# SCH_555-Circuit_2025-12-09_1.net
KiCad netlist of a schematic drawn in EasyEDA
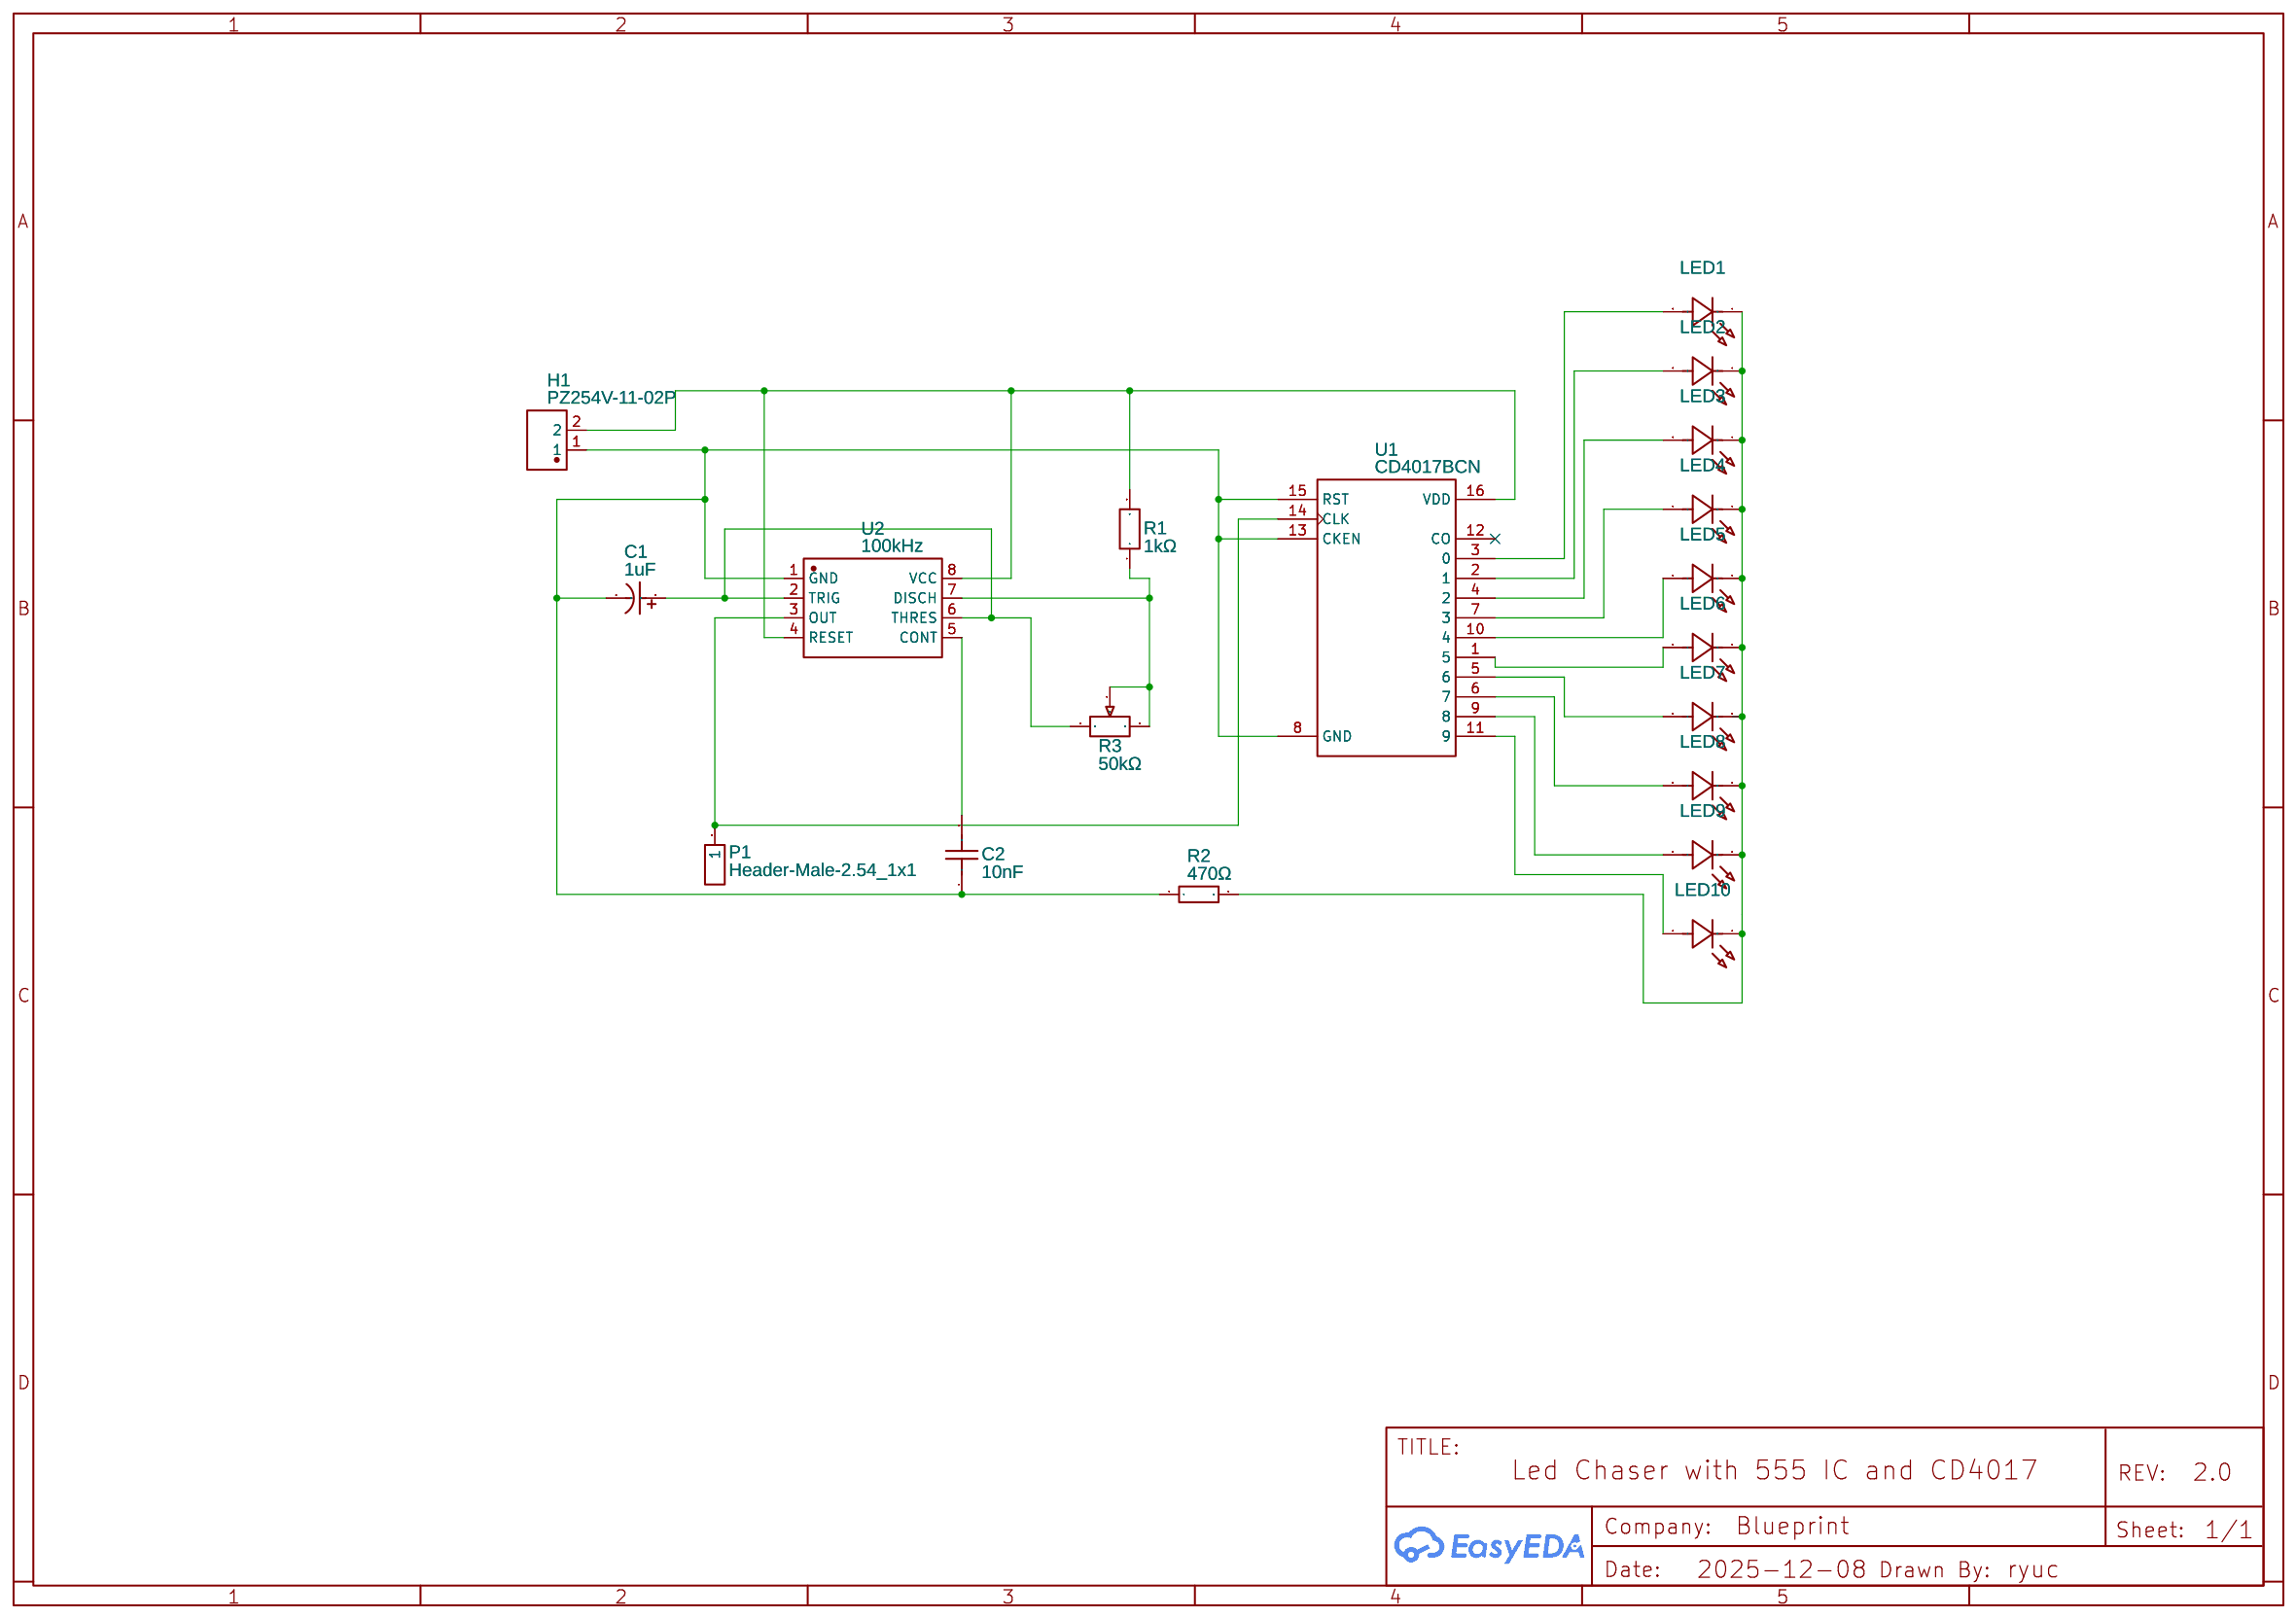
[diagram p0: schematic sheet]

(export (version "E")
  (design (tool "Eeschema 10.0.6"))
  (components
    (comp (ref "C1")
      (value "1uF")
      (fields (field (name "Manufacturer Part") "KF010M050C110A") (field (name "Manufacturer") "CapXon(丰宾)"))
      (libsource (lib "") (part "KF010M050C110A"))
    )
    (comp (ref "C2")
      (value "10nF")
      (fields (field (name "Manufacturer Part") "N09F1B103MN0B0S0N0") (field (name "Manufacturer") "STE(松田)"))
      (libsource (lib "") (part "N09F1B103MN0B0S0N0"))
    )
    (comp (ref "H1")
      (value "PZ254V-11-02P")
      (fields (field (name "Manufacturer") "XFCN(兴飞)"))
      (libsource (lib "") (part "PZ254V-11-02P"))
    )
    (comp (ref "LED1")
      (value "XL-502UWC")
      (fields (field (name "Manufacturer") "XINGLIGHT(成兴光)"))
      (libsource (lib "") (part "XL-502UWC"))
    )
    (comp (ref "LED2")
      (value "XL-502UWC")
      (fields (field (name "Manufacturer") "XINGLIGHT(成兴光)"))
      (libsource (lib "") (part "XL-502UWC"))
    )
    (comp (ref "LED3")
      (value "XL-502UWC")
      (fields (field (name "Manufacturer") "XINGLIGHT(成兴光)"))
      (libsource (lib "") (part "XL-502UWC"))
    )
    (comp (ref "LED4")
      (value "XL-502UWC")
      (fields (field (name "Manufacturer") "XINGLIGHT(成兴光)"))
      (libsource (lib "") (part "XL-502UWC"))
    )
    (comp (ref "LED5")
      (value "XL-502UWC")
      (fields (field (name "Manufacturer") "XINGLIGHT(成兴光)"))
      (libsource (lib "") (part "XL-502UWC"))
    )
    (comp (ref "LED6")
      (value "XL-502UWC")
      (fields (field (name "Manufacturer") "XINGLIGHT(成兴光)"))
      (libsource (lib "") (part "XL-502UWC"))
    )
    (comp (ref "LED7")
      (value "XL-502UWC")
      (fields (field (name "Manufacturer") "XINGLIGHT(成兴光)"))
      (libsource (lib "") (part "XL-502UWC"))
    )
    (comp (ref "LED8")
      (value "XL-502UWC")
      (fields (field (name "Manufacturer") "XINGLIGHT(成兴光)"))
      (libsource (lib "") (part "XL-502UWC"))
    )
    (comp (ref "LED9")
      (value "XL-502UWC")
      (fields (field (name "Manufacturer") "XINGLIGHT(成兴光)"))
      (libsource (lib "") (part "XL-502UWC"))
    )
    (comp (ref "LED10")
      (value "XL-502UWC")
      (fields (field (name "Manufacturer") "XINGLIGHT(成兴光)"))
      (libsource (lib "") (part "XL-502UWC"))
    )
    (comp (ref "P1")
      (value "Header-Male-2.54_1x1")
      (fields (field (name "Manufacturer Part") "2.54-1*1P针") (field (name "Manufacturer") "BOOMELE(博穆精密)"))
      (libsource (lib "") (part "Header-Male-2.54_1x1"))
    )
    (comp (ref "R1")
      (value "1kΩ")
      (fields (field (name "Manufacturer Part") "MF1/4W-1KΩ±1%T52") (field (name "Manufacturer") "华星机电"))
      (libsource (lib "") (part "MF1/4W-1KΩ±1%T52"))
    )
    (comp (ref "R2")
      (value "470Ω")
      (fields
        (field (name "Manufacturer Part") "MFR0W4F4700A50")
        (field (name "Manufacturer") "UNI-ROYAL(厚声)")
      )
      (libsource (lib "") (part "MFR0W4F4700A50"))
    )
    (comp (ref "R3")
      (value "50kΩ")
      (fields (field (name "Manufacturer Part") "3296X-1-503") (field (name "Manufacturer") "BOCHEN(博晨)"))
      (libsource (lib "") (part "3296X-1-503_C118912"))
    )
    (comp (ref "U1") (value "CD4017BCN") (libsource (lib "") (part "CD4017BCN")))
    (comp (ref "U2")
      (value "100kHz")
      (fields (field (name "Manufacturer Part") "NE555P") (field (name "Manufacturer") "TI(德州仪器)"))
      (libsource (lib "") (part "NE555P"))
    )
  )
  (nets
    (net (code "1") (name "Net-(LED1-A)") (class "Default")
      (node (ref "LED1") (pin "2") (pinfunction "A_2") (pintype "unspecified"))
      (node (ref "U1") (pin "3") (pinfunction "0_3") (pintype "output"))
    )
    (net (code "2") (name "Net-(LED1-K)") (class "Default")
      (node (ref "LED1") (pin "1") (pinfunction "K_1") (pintype "unspecified"))
      (node (ref "LED10") (pin "1") (pinfunction "K_1") (pintype "unspecified"))
      (node (ref "LED2") (pin "1") (pinfunction "K_1") (pintype "unspecified"))
      (node (ref "LED3") (pin "1") (pinfunction "K_1") (pintype "unspecified"))
      (node (ref "LED4") (pin "1") (pinfunction "K_1") (pintype "unspecified"))
      (node (ref "LED5") (pin "1") (pinfunction "K_1") (pintype "unspecified"))
      (node (ref "LED6") (pin "1") (pinfunction "K_1") (pintype "unspecified"))
      (node (ref "LED7") (pin "1") (pinfunction "K_1") (pintype "unspecified"))
      (node (ref "LED8") (pin "1") (pinfunction "K_1") (pintype "unspecified"))
      (node (ref "LED9") (pin "1") (pinfunction "K_1") (pintype "unspecified"))
      (node (ref "R2") (pin "2") (pinfunction "2_2") (pintype "input"))
    )
    (net (code "3") (name "Net-(LED2-A)") (class "Default")
      (node (ref "LED2") (pin "2") (pinfunction "A_2") (pintype "unspecified"))
      (node (ref "U1") (pin "2") (pinfunction "1_2") (pintype "output"))
    )
    (net (code "4") (name "Net-(LED3-A)") (class "Default")
      (node (ref "LED3") (pin "2") (pinfunction "A_2") (pintype "unspecified"))
      (node (ref "U1") (pin "4") (pinfunction "2_4") (pintype "output"))
    )
    (net (code "5") (name "Net-(LED4-A)") (class "Default")
      (node (ref "LED4") (pin "2") (pinfunction "A_2") (pintype "unspecified"))
      (node (ref "U1") (pin "7") (pinfunction "3_7") (pintype "output"))
    )
    (net (code "6") (name "Net-(LED5-A)") (class "Default")
      (node (ref "LED5") (pin "2") (pinfunction "A_2") (pintype "unspecified"))
      (node (ref "U1") (pin "10") (pinfunction "4_10") (pintype "output"))
    )
    (net (code "7") (name "Net-(LED6-A)") (class "Default")
      (node (ref "LED6") (pin "2") (pinfunction "A_2") (pintype "unspecified"))
      (node (ref "U1") (pin "1") (pinfunction "5_1") (pintype "output"))
    )
    (net (code "8") (name "Net-(LED7-A)") (class "Default")
      (node (ref "LED7") (pin "2") (pinfunction "A_2") (pintype "unspecified"))
      (node (ref "U1") (pin "5") (pinfunction "6_5") (pintype "output"))
    )
    (net (code "9") (name "Net-(LED8-A)") (class "Default")
      (node (ref "LED8") (pin "2") (pinfunction "A_2") (pintype "unspecified"))
      (node (ref "U1") (pin "6") (pinfunction "7_6") (pintype "output"))
    )
    (net (code "10") (name "Net-(LED9-A)") (class "Default")
      (node (ref "LED9") (pin "2") (pinfunction "A_2") (pintype "unspecified"))
      (node (ref "U1") (pin "9") (pinfunction "8_9") (pintype "output"))
    )
    (net (code "11") (name "Net-(LED10-A)") (class "Default")
      (node (ref "LED10") (pin "2") (pinfunction "A_2") (pintype "unspecified"))
      (node (ref "U1") (pin "11") (pinfunction "9_11") (pintype "output"))
    )
    (net (code "12") (name "Net-(U1-CKEN)") (class "Default")
      (node (ref "C1") (pin "2") (pinfunction "2_2") (pintype "input"))
      (node (ref "C2") (pin "1") (pinfunction "1_1") (pintype "unspecified"))
      (node (ref "H1") (pin "1") (pinfunction "1_1") (pintype "unspecified"))
      (node (ref "R2") (pin "1") (pinfunction "1_1") (pintype "input"))
      (node (ref "U1") (pin "13") (pinfunction "CKEN_13") (pintype "unspecified"))
      (node (ref "U1") (pin "15") (pinfunction "RST_15") (pintype "unspecified"))
      (node (ref "U1") (pin "8") (pinfunction "GND_8") (pintype "passive"))
      (node (ref "U2") (pin "1") (pinfunction "GND_1") (pintype "unspecified"))
    )
    (net (code "13") (name "Net-(U1-CLK)") (class "Default")
      (node (ref "P1") (pin "1") (pinfunction "1_1") (pintype "input"))
      (node (ref "U1") (pin "14") (pinfunction "CLK_14") (pintype "unspecified"))
      (node (ref "U2") (pin "3") (pinfunction "OUT_3") (pintype "unspecified"))
    )
    (net (code "14") (name "Net-(U1-VDD)") (class "Default")
      (node (ref "H1") (pin "2") (pinfunction "2_2") (pintype "unspecified"))
      (node (ref "R1") (pin "2") (pinfunction "2_2") (pintype "unspecified"))
      (node (ref "U1") (pin "16") (pinfunction "VDD_16") (pintype "passive"))
      (node (ref "U2") (pin "4") (pinfunction "RESET_4") (pintype "unspecified"))
      (node (ref "U2") (pin "8") (pinfunction "VCC_8") (pintype "unspecified"))
    )
    (net (code "15") (name "Net-(U2-CONT)") (class "Default")
      (node (ref "C2") (pin "2") (pinfunction "2_2") (pintype "unspecified"))
      (node (ref "U2") (pin "5") (pinfunction "CONT_5") (pintype "unspecified"))
    )
    (net (code "16") (name "Net-(U2-DISCH)") (class "Default")
      (node (ref "R1") (pin "1") (pinfunction "1_1") (pintype "unspecified"))
      (node (ref "R3") (pin "2") (pinfunction "2_2") (pintype "input"))
      (node (ref "R3") (pin "3") (pinfunction "3_3") (pintype "input"))
      (node (ref "U2") (pin "7") (pinfunction "DISCH_7") (pintype "unspecified"))
    )
    (net (code "17") (name "Net-(U2-THRES)") (class "Default")
      (node (ref "C1") (pin "1") (pinfunction "1_1") (pintype "input"))
      (node (ref "R3") (pin "1") (pinfunction "1_1") (pintype "input"))
      (node (ref "U2") (pin "2") (pinfunction "TRIG_2") (pintype "unspecified"))
      (node (ref "U2") (pin "6") (pinfunction "THRES_6") (pintype "unspecified"))
    )
    (net (code "18") (name "unconnected-(U1-CO-Pad12)") (class "Default")
      (node (ref "U1") (pin "12") (pinfunction "CO_12") (pintype "output+no_connect"))
    )
  )
)
